# sdls.net
KiCad netlist of a schematic drawn in EAGLE
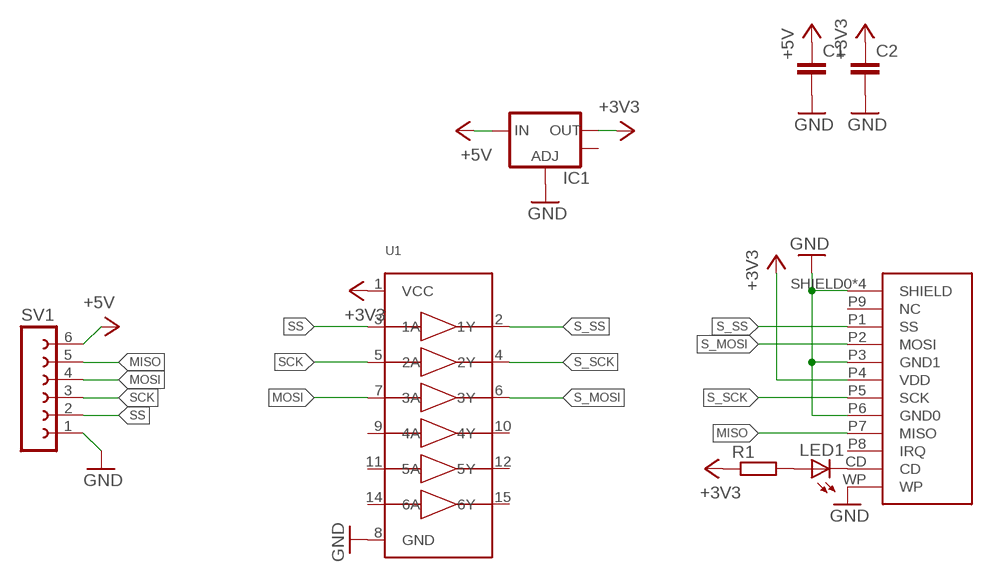
[diagram p0: schematic, sheet 1]

(export (version "E")
  (design (tool "Eeschema 10.0.6"))
  (components
    (comp (ref "C1")
      (value "C-EUC0805K")
      (footprint "eagle-import:C0805K")
      (libsource (lib "eagle-import") (part "C-EUC0805K"))
    )
    (comp (ref "C2")
      (value "C-EUC0805K")
      (footprint "eagle-import:C0805K")
      (libsource (lib "eagle-import") (part "C-EUC0805K"))
    )
    (comp (ref "IC1")
      (value "V_REG_LM1117SOT223")
      (footprint "eagle-import:SOT223")
      (libsource (lib "eagle-import") (part "V_REG_LM1117SOT223"))
    )
    (comp (ref "LED1")
      (value "LEDSML0805")
      (footprint "eagle-import:SML0805")
      (libsource (lib "eagle-import") (part "LEDSML0805"))
    )
    (comp (ref "R1")
      (value "R-EU_R0603")
      (footprint "eagle-import:R0603")
      (libsource (lib "eagle-import") (part "R-EU_R0603"))
    )
    (comp (ref "SV1")
      (value "FE06-1")
      (footprint "eagle-import:FE06")
      (libsource (lib "eagle-import") (part "FE06-1"))
    )
    (comp (ref "U$1")
      (value "SD_CARD")
      (footprint "eagle-import:MEM1055")
      (libsource (lib "eagle-import") (part "SD_CARD"))
    )
    (comp (ref "U1")
      (value "74HC4050D")
      (footprint "eagle-import:SOIC16")
      (libsource (lib "eagle-import") (part "74HC4050D"))
    )
  )
  (nets
    (net (code "1") (name "+3V3") (class "Default")
      (node (ref "C2") (pin "1") (pinfunction "1_1") (pintype "passive"))
      (node (ref "IC1") (pin "2") (pinfunction "OUT_2") (pintype "output"))
      (node (ref "R1") (pin "1") (pinfunction "1_1") (pintype "passive"))
      (node (ref "U$1") (pin "P4") (pinfunction "VDD_P4") (pintype "bidirectional"))
      (node (ref "U1") (pin "1") (pinfunction "VCC_1") (pintype "bidirectional"))
    )
    (net (code "2") (name "+5V") (class "Default")
      (node (ref "C1") (pin "1") (pinfunction "1_1") (pintype "passive"))
      (node (ref "IC1") (pin "3") (pinfunction "IN_3") (pintype "input"))
      (node (ref "SV1") (pin "6") (pinfunction "6_6") (pintype "passive"))
    )
    (net (code "3") (name "GND") (class "Default")
      (node (ref "C1") (pin "2") (pinfunction "2_2") (pintype "passive"))
      (node (ref "C2") (pin "2") (pinfunction "2_2") (pintype "passive"))
      (node (ref "IC1") (pin "1") (pinfunction "ADJ_1") (pintype "input"))
      (node (ref "SV1") (pin "1") (pinfunction "1_1") (pintype "passive"))
      (node (ref "U$1") (pin "P3") (pinfunction "GND1_P3") (pintype "bidirectional"))
      (node (ref "U$1") (pin "P6") (pinfunction "GND0_P6") (pintype "bidirectional"))
      (node (ref "U$1") (pin "SHIELD0") (pinfunction "SHIELD_SHIELD0") (pintype "bidirectional"))
      (node (ref "U$1") (pin "SHIELD1") (pinfunction "SHIELD_SHIELD1") (pintype "bidirectional"))
      (node (ref "U$1") (pin "SHIELD2") (pinfunction "SHIELD_SHIELD2") (pintype "bidirectional"))
      (node (ref "U$1") (pin "SHIELD3") (pinfunction "SHIELD_SHIELD3") (pintype "bidirectional"))
      (node (ref "U$1") (pin "WP") (pinfunction "WP_WP") (pintype "bidirectional"))
      (node (ref "U1") (pin "8") (pinfunction "GND_8") (pintype "bidirectional"))
    )
    (net (code "4") (name "MISO") (class "Default")
      (node (ref "SV1") (pin "5") (pinfunction "5_5") (pintype "passive"))
      (node (ref "U$1") (pin "P7") (pinfunction "MISO_P7") (pintype "bidirectional"))
    )
    (net (code "5") (name "MOSI") (class "Default")
      (node (ref "SV1") (pin "4") (pinfunction "4_4") (pintype "passive"))
      (node (ref "U1") (pin "7") (pinfunction "3A_7") (pintype "bidirectional"))
    )
    (net (code "6") (name "Net-(LED1-PadA)") (class "Default")
      (node (ref "LED1") (pin "A") (pinfunction "A_A") (pintype "passive"))
      (node (ref "R1") (pin "2") (pinfunction "2_2") (pintype "passive"))
    )
    (net (code "7") (name "Net-(LED1-PadC)") (class "Default")
      (node (ref "LED1") (pin "C") (pinfunction "C_C") (pintype "passive"))
      (node (ref "U$1") (pin "CD") (pinfunction "CD_CD") (pintype "bidirectional"))
    )
    (net (code "8") (name "SCK") (class "Default")
      (node (ref "SV1") (pin "3") (pinfunction "3_3") (pintype "passive"))
      (node (ref "U1") (pin "5") (pinfunction "2A_5") (pintype "bidirectional"))
    )
    (net (code "9") (name "SS") (class "Default")
      (node (ref "SV1") (pin "2") (pinfunction "2_2") (pintype "passive"))
      (node (ref "U1") (pin "3") (pinfunction "1A_3") (pintype "bidirectional"))
    )
    (net (code "10") (name "S_MOSI") (class "Default")
      (node (ref "U$1") (pin "P2") (pinfunction "MOSI_P2") (pintype "bidirectional"))
      (node (ref "U1") (pin "6") (pinfunction "3Y_6") (pintype "bidirectional"))
    )
    (net (code "11") (name "S_SCK") (class "Default")
      (node (ref "U$1") (pin "P5") (pinfunction "SCK_P5") (pintype "bidirectional"))
      (node (ref "U1") (pin "4") (pinfunction "2Y_4") (pintype "bidirectional"))
    )
    (net (code "12") (name "S_SS") (class "Default")
      (node (ref "U$1") (pin "P1") (pinfunction "SS_P1") (pintype "bidirectional"))
      (node (ref "U1") (pin "2") (pinfunction "1Y_2") (pintype "bidirectional"))
    )
    (net (code "13") (name "unconnected-(IC1-OUT-Pad4)") (class "Default")
      (node (ref "IC1") (pin "4") (pinfunction "OUT_4") (pintype "output"))
    )
    (net (code "14") (name "unconnected-(U$1-IRQ-PadP8)") (class "Default")
      (node (ref "U$1") (pin "P8") (pinfunction "IRQ_P8") (pintype "bidirectional"))
    )
    (net (code "15") (name "unconnected-(U$1-NC-PadP9)") (class "Default")
      (node (ref "U$1") (pin "P9") (pinfunction "NC_P9") (pintype "bidirectional"))
    )
    (net (code "16") (name "unconnected-(U1-4A-Pad9)") (class "Default")
      (node (ref "U1") (pin "9") (pinfunction "4A_9") (pintype "bidirectional"))
    )
    (net (code "17") (name "unconnected-(U1-4Y-Pad10)") (class "Default")
      (node (ref "U1") (pin "10") (pinfunction "4Y_10") (pintype "bidirectional"))
    )
    (net (code "18") (name "unconnected-(U1-5A-Pad11)") (class "Default")
      (node (ref "U1") (pin "11") (pinfunction "5A_11") (pintype "bidirectional"))
    )
    (net (code "19") (name "unconnected-(U1-5Y-Pad12)") (class "Default")
      (node (ref "U1") (pin "12") (pinfunction "5Y_12") (pintype "bidirectional"))
    )
    (net (code "20") (name "unconnected-(U1-6A-Pad14)") (class "Default")
      (node (ref "U1") (pin "14") (pinfunction "6A_14") (pintype "bidirectional"))
    )
    (net (code "21") (name "unconnected-(U1-6Y-Pad15)") (class "Default")
      (node (ref "U1") (pin "15") (pinfunction "6Y_15") (pintype "bidirectional"))
    )
  )
)
